# Ignitor_Outputs.net
KiCad netlist of a schematic drawn in Altium Designer
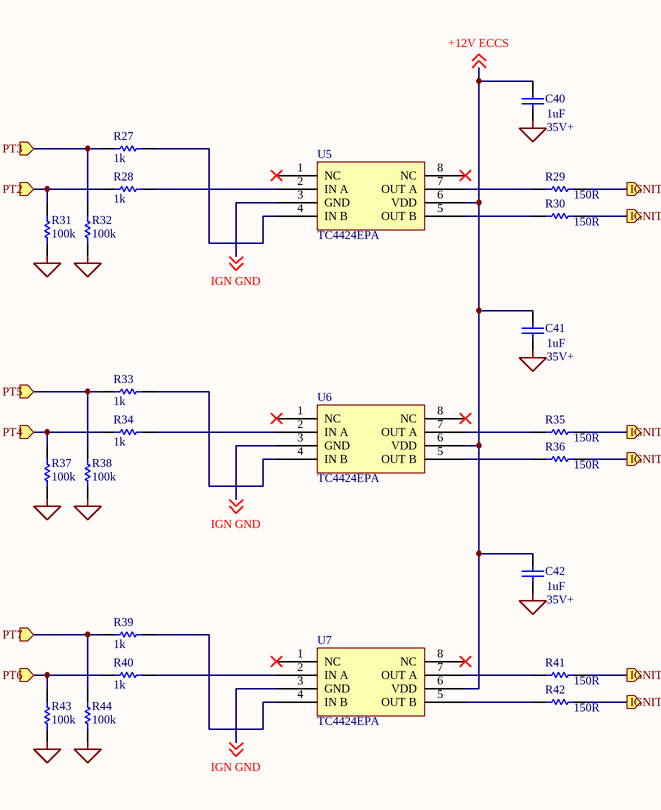
[diagram p0: Ignitor Outputs.SchDoc]

(export (version "E")
  (design (tool "Eeschema 10.0.6"))
  (components
    (comp (ref "C40")
      (value "1uF")
      (footprint "RAD-0.3")
      (description "Capacitor")
      (fields (field (name "PUBLISHER") "Altium Limited"))
      (libsource (lib "Miscellaneous Devices") (part "Cap"))
    )
    (comp (ref "C41")
      (value "1uF")
      (footprint "RAD-0.3")
      (description "Capacitor")
      (fields (field (name "PUBLISHER") "Altium Limited"))
      (libsource (lib "Miscellaneous Devices") (part "Cap"))
    )
    (comp (ref "C42")
      (value "1uF")
      (footprint "RAD-0.3")
      (description "Capacitor")
      (fields (field (name "PUBLISHER") "Altium Limited"))
      (libsource (lib "Miscellaneous Devices") (part "Cap"))
    )
    (comp (ref "R27")
      (value "1k")
      (footprint "AXIAL-0.3")
      (description "Resistor")
      (fields (field (name "PUBLISHER") "Altium Limited"))
      (libsource (lib "Miscellaneous Devices") (part "Res1"))
    )
    (comp (ref "R28")
      (value "1k")
      (footprint "AXIAL-0.3")
      (description "Resistor")
      (fields (field (name "PUBLISHER") "Altium Limited"))
      (libsource (lib "Miscellaneous Devices") (part "Res1"))
    )
    (comp (ref "R29")
      (value "150R")
      (footprint "AXIAL-0.3")
      (description "Resistor")
      (fields (field (name "PUBLISHER") "Altium Limited"))
      (libsource (lib "Miscellaneous Devices") (part "Res1"))
    )
    (comp (ref "R30")
      (value "150R")
      (footprint "AXIAL-0.3")
      (description "Resistor")
      (fields (field (name "PUBLISHER") "Altium Limited"))
      (libsource (lib "Miscellaneous Devices") (part "Res1"))
    )
    (comp (ref "R31")
      (value "100k")
      (footprint "AXIAL-0.3")
      (description "Resistor")
      (fields (field (name "PUBLISHER") "Altium Limited"))
      (libsource (lib "Miscellaneous Devices") (part "Res1"))
    )
    (comp (ref "R32")
      (value "100k")
      (footprint "AXIAL-0.3")
      (description "Resistor")
      (fields (field (name "PUBLISHER") "Altium Limited"))
      (libsource (lib "Miscellaneous Devices") (part "Res1"))
    )
    (comp (ref "R33")
      (value "1k")
      (footprint "AXIAL-0.3")
      (description "Resistor")
      (fields (field (name "PUBLISHER") "Altium Limited"))
      (libsource (lib "Miscellaneous Devices") (part "Res1"))
    )
    (comp (ref "R34")
      (value "1k")
      (footprint "AXIAL-0.3")
      (description "Resistor")
      (fields (field (name "PUBLISHER") "Altium Limited"))
      (libsource (lib "Miscellaneous Devices") (part "Res1"))
    )
    (comp (ref "R35")
      (value "150R")
      (footprint "AXIAL-0.3")
      (description "Resistor")
      (fields (field (name "PUBLISHER") "Altium Limited"))
      (libsource (lib "Miscellaneous Devices") (part "Res1"))
    )
    (comp (ref "R36")
      (value "150R")
      (footprint "AXIAL-0.3")
      (description "Resistor")
      (fields (field (name "PUBLISHER") "Altium Limited"))
      (libsource (lib "Miscellaneous Devices") (part "Res1"))
    )
    (comp (ref "R37")
      (value "100k")
      (footprint "AXIAL-0.3")
      (description "Resistor")
      (fields (field (name "PUBLISHER") "Altium Limited"))
      (libsource (lib "Miscellaneous Devices") (part "Res1"))
    )
    (comp (ref "R38")
      (value "100k")
      (footprint "AXIAL-0.3")
      (description "Resistor")
      (fields (field (name "PUBLISHER") "Altium Limited"))
      (libsource (lib "Miscellaneous Devices") (part "Res1"))
    )
    (comp (ref "R39")
      (value "1k")
      (footprint "AXIAL-0.3")
      (description "Resistor")
      (fields (field (name "PUBLISHER") "Altium Limited"))
      (libsource (lib "Miscellaneous Devices") (part "Res1"))
    )
    (comp (ref "R40")
      (value "1k")
      (footprint "AXIAL-0.3")
      (description "Resistor")
      (fields (field (name "PUBLISHER") "Altium Limited"))
      (libsource (lib "Miscellaneous Devices") (part "Res1"))
    )
    (comp (ref "R41")
      (value "150R")
      (footprint "AXIAL-0.3")
      (description "Resistor")
      (fields (field (name "PUBLISHER") "Altium Limited"))
      (libsource (lib "Miscellaneous Devices") (part "Res1"))
    )
    (comp (ref "R42")
      (value "150R")
      (footprint "AXIAL-0.3")
      (description "Resistor")
      (fields (field (name "PUBLISHER") "Altium Limited"))
      (libsource (lib "Miscellaneous Devices") (part "Res1"))
    )
    (comp (ref "R43")
      (value "100k")
      (footprint "AXIAL-0.3")
      (description "Resistor")
      (fields (field (name "PUBLISHER") "Altium Limited"))
      (libsource (lib "Miscellaneous Devices") (part "Res1"))
    )
    (comp (ref "R44")
      (value "100k")
      (footprint "AXIAL-0.3")
      (description "Resistor")
      (fields (field (name "PUBLISHER") "Altium Limited"))
      (libsource (lib "Miscellaneous Devices") (part "Res1"))
    )
    (comp (ref "U5") (value "TC4424EPA") (libsource (lib "FreeEMS Schematic Library") (part "TC427COA")))
    (comp (ref "U6") (value "TC4424EPA") (libsource (lib "FreeEMS Schematic Library") (part "TC427COA")))
    (comp (ref "U7") (value "TC4424EPA") (libsource (lib "FreeEMS Schematic Library") (part "TC427COA")))
  )
  (nets
    (net (code "1") (name "+12V ECCS") (class "Default")
      (node (ref "C40") (pin "2") (pinfunction "2_2") (pintype "passive"))
      (node (ref "C41") (pin "2") (pinfunction "2_2") (pintype "passive"))
      (node (ref "C42") (pin "2") (pinfunction "2_2") (pintype "passive"))
      (node (ref "U5") (pin "6") (pinfunction "VDD_6") (pintype "passive"))
      (node (ref "U6") (pin "6") (pinfunction "VDD_6") (pintype "passive"))
      (node (ref "U7") (pin "6") (pinfunction "VDD_6") (pintype "passive"))
    )
    (net (code "2") (name "/IGNITOR 1") (class "Default")
      (node (ref "R29") (pin "2") (pinfunction "2_2") (pintype "passive"))
    )
    (net (code "3") (name "/IGNITOR 2") (class "Default")
      (node (ref "R30") (pin "2") (pinfunction "2_2") (pintype "passive"))
    )
    (net (code "4") (name "/IGNITOR 3") (class "Default")
      (node (ref "R35") (pin "2") (pinfunction "2_2") (pintype "passive"))
    )
    (net (code "5") (name "/IGNITOR 4") (class "Default")
      (node (ref "R36") (pin "2") (pinfunction "2_2") (pintype "passive"))
    )
    (net (code "6") (name "/IGNITOR 5") (class "Default")
      (node (ref "R41") (pin "2") (pinfunction "2_2") (pintype "passive"))
    )
    (net (code "7") (name "/IGNITOR 6") (class "Default")
      (node (ref "R42") (pin "2") (pinfunction "2_2") (pintype "passive"))
    )
    (net (code "8") (name "/PT2") (class "Default")
      (node (ref "R28") (pin "2") (pinfunction "2_2") (pintype "passive"))
      (node (ref "R31") (pin "2") (pinfunction "2_2") (pintype "passive"))
    )
    (net (code "9") (name "/PT3") (class "Default")
      (node (ref "R27") (pin "2") (pinfunction "2_2") (pintype "passive"))
      (node (ref "R32") (pin "2") (pinfunction "2_2") (pintype "passive"))
    )
    (net (code "10") (name "/PT4") (class "Default")
      (node (ref "R34") (pin "2") (pinfunction "2_2") (pintype "passive"))
      (node (ref "R37") (pin "2") (pinfunction "2_2") (pintype "passive"))
    )
    (net (code "11") (name "/PT5") (class "Default")
      (node (ref "R33") (pin "2") (pinfunction "2_2") (pintype "passive"))
      (node (ref "R38") (pin "2") (pinfunction "2_2") (pintype "passive"))
    )
    (net (code "12") (name "/PT6") (class "Default")
      (node (ref "R40") (pin "2") (pinfunction "2_2") (pintype "passive"))
      (node (ref "R43") (pin "2") (pinfunction "2_2") (pintype "passive"))
    )
    (net (code "13") (name "/PT7") (class "Default")
      (node (ref "R39") (pin "2") (pinfunction "2_2") (pintype "passive"))
      (node (ref "R44") (pin "2") (pinfunction "2_2") (pintype "passive"))
    )
    (net (code "14") (name "<NO NET>") (class "Default")
      (node (ref "C40") (pin "1") (pinfunction "1_1") (pintype "passive"))
      (node (ref "C41") (pin "1") (pinfunction "1_1") (pintype "passive"))
      (node (ref "C42") (pin "1") (pinfunction "1_1") (pintype "passive"))
      (node (ref "R31") (pin "1") (pinfunction "1_1") (pintype "passive"))
      (node (ref "R32") (pin "1") (pinfunction "1_1") (pintype "passive"))
      (node (ref "R37") (pin "1") (pinfunction "1_1") (pintype "passive"))
      (node (ref "R38") (pin "1") (pinfunction "1_1") (pintype "passive"))
      (node (ref "R43") (pin "1") (pinfunction "1_1") (pintype "passive"))
      (node (ref "R44") (pin "1") (pinfunction "1_1") (pintype "passive"))
    )
    (net (code "15") (name "IGN GND") (class "Default")
      (node (ref "U5") (pin "3") (pinfunction "GND_3") (pintype "passive"))
      (node (ref "U6") (pin "3") (pinfunction "GND_3") (pintype "passive"))
      (node (ref "U7") (pin "3") (pinfunction "GND_3") (pintype "passive"))
    )
    (net (code "16") (name "Net-(U5-IN_A)") (class "Default")
      (node (ref "R28") (pin "1") (pinfunction "1_1") (pintype "passive"))
      (node (ref "U5") (pin "2") (pinfunction "IN_A_2") (pintype "passive"))
    )
    (net (code "17") (name "Net-(U5-IN_B)") (class "Default")
      (node (ref "R27") (pin "1") (pinfunction "1_1") (pintype "passive"))
      (node (ref "U5") (pin "4") (pinfunction "IN_B_4") (pintype "passive"))
    )
    (net (code "18") (name "Net-(U5-OUT_A)") (class "Default")
      (node (ref "R29") (pin "1") (pinfunction "1_1") (pintype "passive"))
      (node (ref "U5") (pin "7") (pinfunction "OUT_A_7") (pintype "passive"))
    )
    (net (code "19") (name "Net-(U5-OUT_B)") (class "Default")
      (node (ref "R30") (pin "1") (pinfunction "1_1") (pintype "passive"))
      (node (ref "U5") (pin "5") (pinfunction "OUT_B_5") (pintype "passive"))
    )
    (net (code "20") (name "Net-(U6-IN_A)") (class "Default")
      (node (ref "R34") (pin "1") (pinfunction "1_1") (pintype "passive"))
      (node (ref "U6") (pin "2") (pinfunction "IN_A_2") (pintype "passive"))
    )
    (net (code "21") (name "Net-(U6-IN_B)") (class "Default")
      (node (ref "R33") (pin "1") (pinfunction "1_1") (pintype "passive"))
      (node (ref "U6") (pin "4") (pinfunction "IN_B_4") (pintype "passive"))
    )
    (net (code "22") (name "Net-(U6-OUT_A)") (class "Default")
      (node (ref "R35") (pin "1") (pinfunction "1_1") (pintype "passive"))
      (node (ref "U6") (pin "7") (pinfunction "OUT_A_7") (pintype "passive"))
    )
    (net (code "23") (name "Net-(U6-OUT_B)") (class "Default")
      (node (ref "R36") (pin "1") (pinfunction "1_1") (pintype "passive"))
      (node (ref "U6") (pin "5") (pinfunction "OUT_B_5") (pintype "passive"))
    )
    (net (code "24") (name "Net-(U7-IN_A)") (class "Default")
      (node (ref "R40") (pin "1") (pinfunction "1_1") (pintype "passive"))
      (node (ref "U7") (pin "2") (pinfunction "IN_A_2") (pintype "passive"))
    )
    (net (code "25") (name "Net-(U7-IN_B)") (class "Default")
      (node (ref "R39") (pin "1") (pinfunction "1_1") (pintype "passive"))
      (node (ref "U7") (pin "4") (pinfunction "IN_B_4") (pintype "passive"))
    )
    (net (code "26") (name "Net-(U7-OUT_A)") (class "Default")
      (node (ref "R41") (pin "1") (pinfunction "1_1") (pintype "passive"))
      (node (ref "U7") (pin "7") (pinfunction "OUT_A_7") (pintype "passive"))
    )
    (net (code "27") (name "Net-(U7-OUT_B)") (class "Default")
      (node (ref "R42") (pin "1") (pinfunction "1_1") (pintype "passive"))
      (node (ref "U7") (pin "5") (pinfunction "OUT_B_5") (pintype "passive"))
    )
    (net (code "28") (name "unconnected-(U5-NC-Pad1)") (class "Default")
      (node (ref "U5") (pin "1") (pinfunction "NC_1") (pintype "passive+no_connect"))
    )
    (net (code "29") (name "unconnected-(U5-NC-Pad8)") (class "Default")
      (node (ref "U5") (pin "8") (pinfunction "NC_8") (pintype "passive+no_connect"))
    )
    (net (code "30") (name "unconnected-(U6-NC-Pad1)") (class "Default")
      (node (ref "U6") (pin "1") (pinfunction "NC_1") (pintype "passive+no_connect"))
    )
    (net (code "31") (name "unconnected-(U6-NC-Pad8)") (class "Default")
      (node (ref "U6") (pin "8") (pinfunction "NC_8") (pintype "passive+no_connect"))
    )
    (net (code "32") (name "unconnected-(U7-NC-Pad1)") (class "Default")
      (node (ref "U7") (pin "1") (pinfunction "NC_1") (pintype "passive+no_connect"))
    )
    (net (code "33") (name "unconnected-(U7-NC-Pad8)") (class "Default")
      (node (ref "U7") (pin "8") (pinfunction "NC_8") (pintype "passive+no_connect"))
    )
  )
)
